# peaks_v02.net
KiCad netlist of a schematic drawn in EAGLE
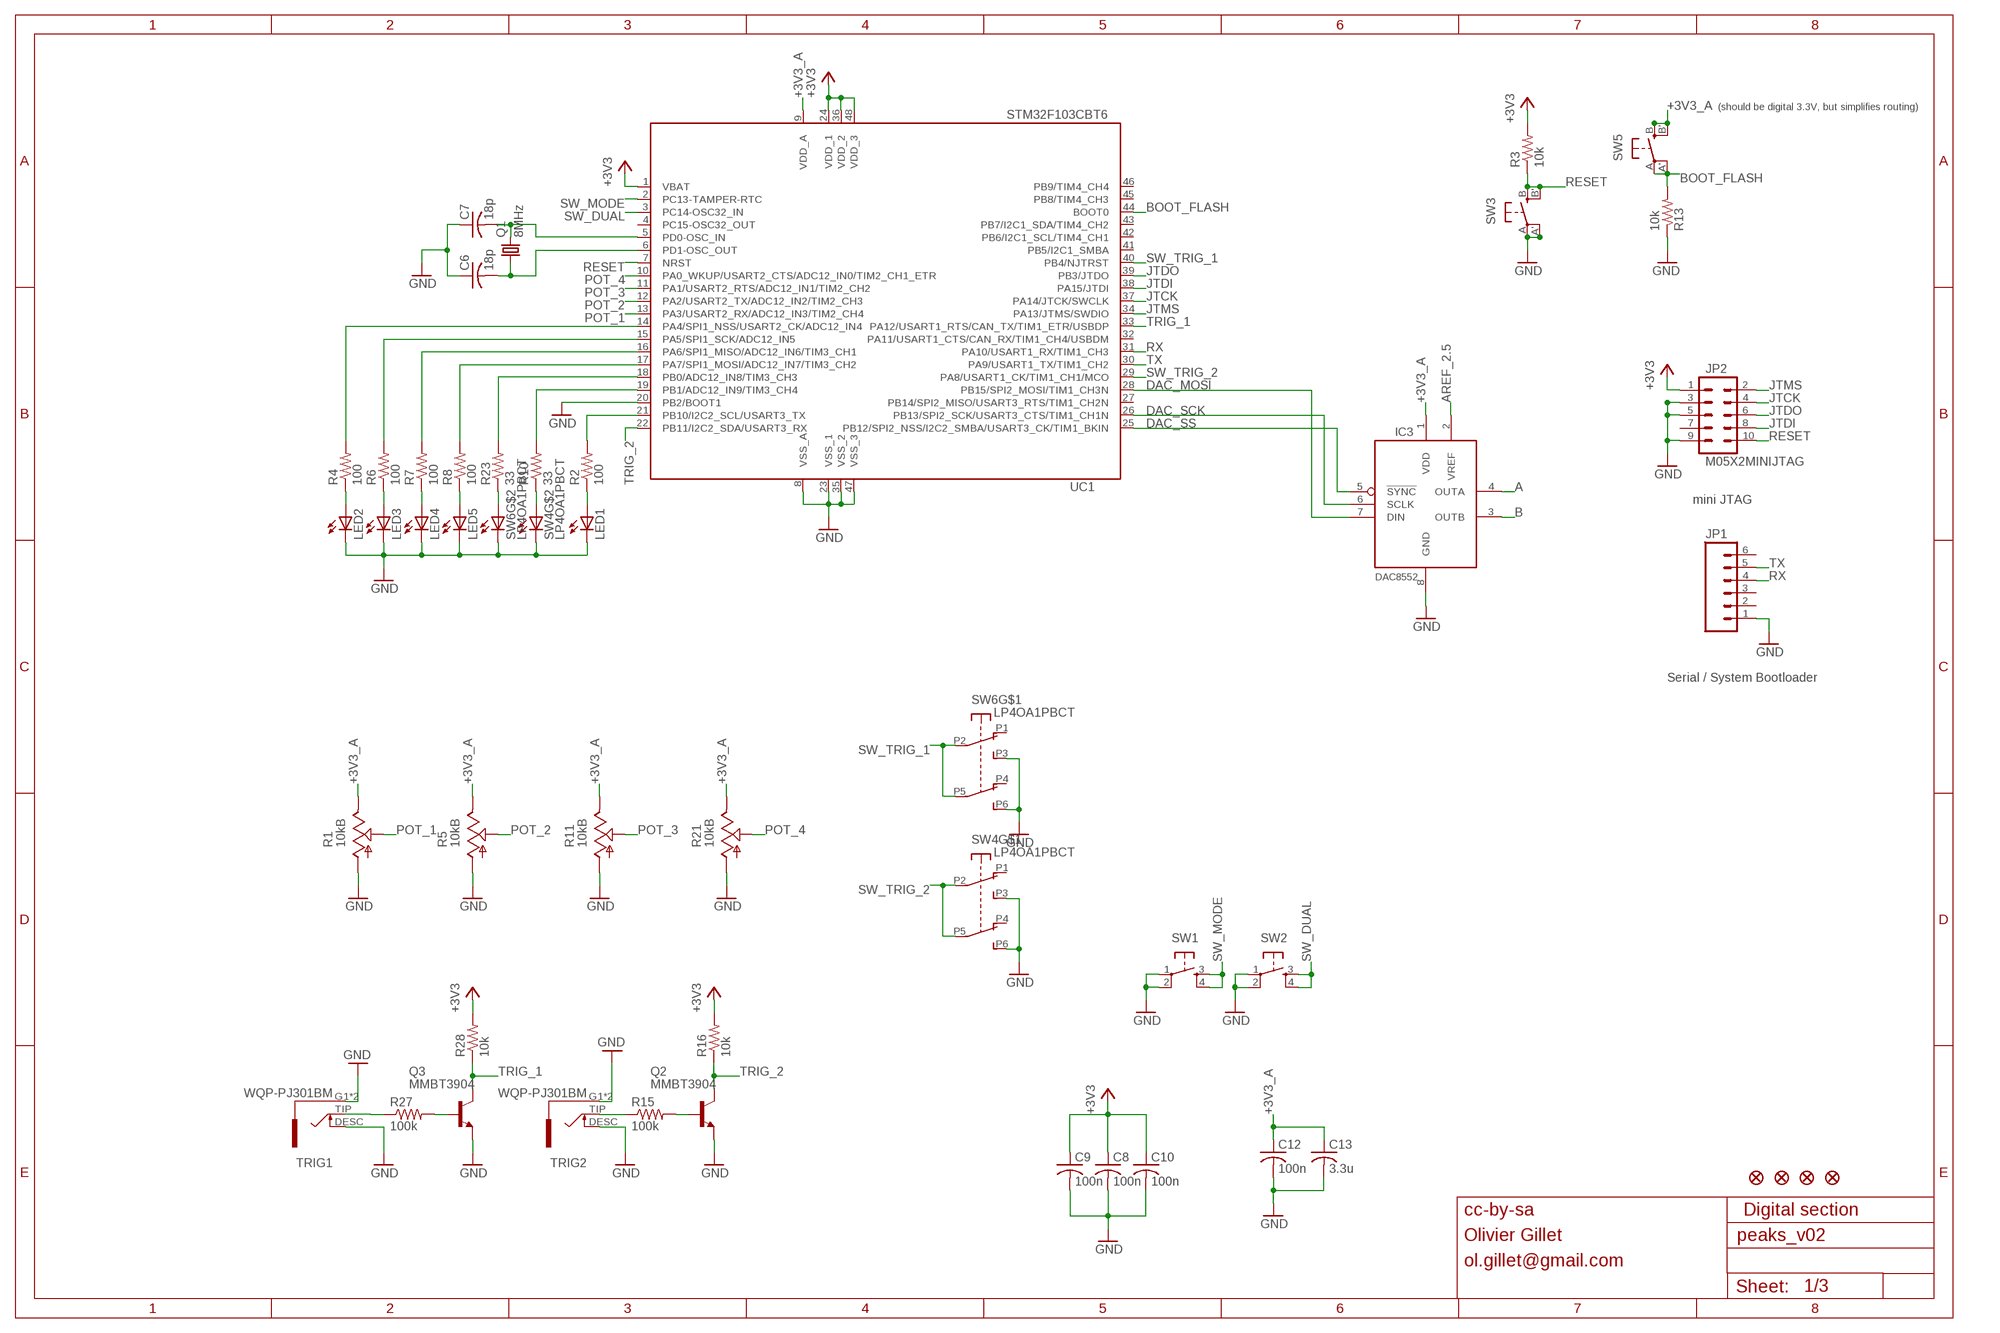
[diagram p0: schematic, sheet 1]
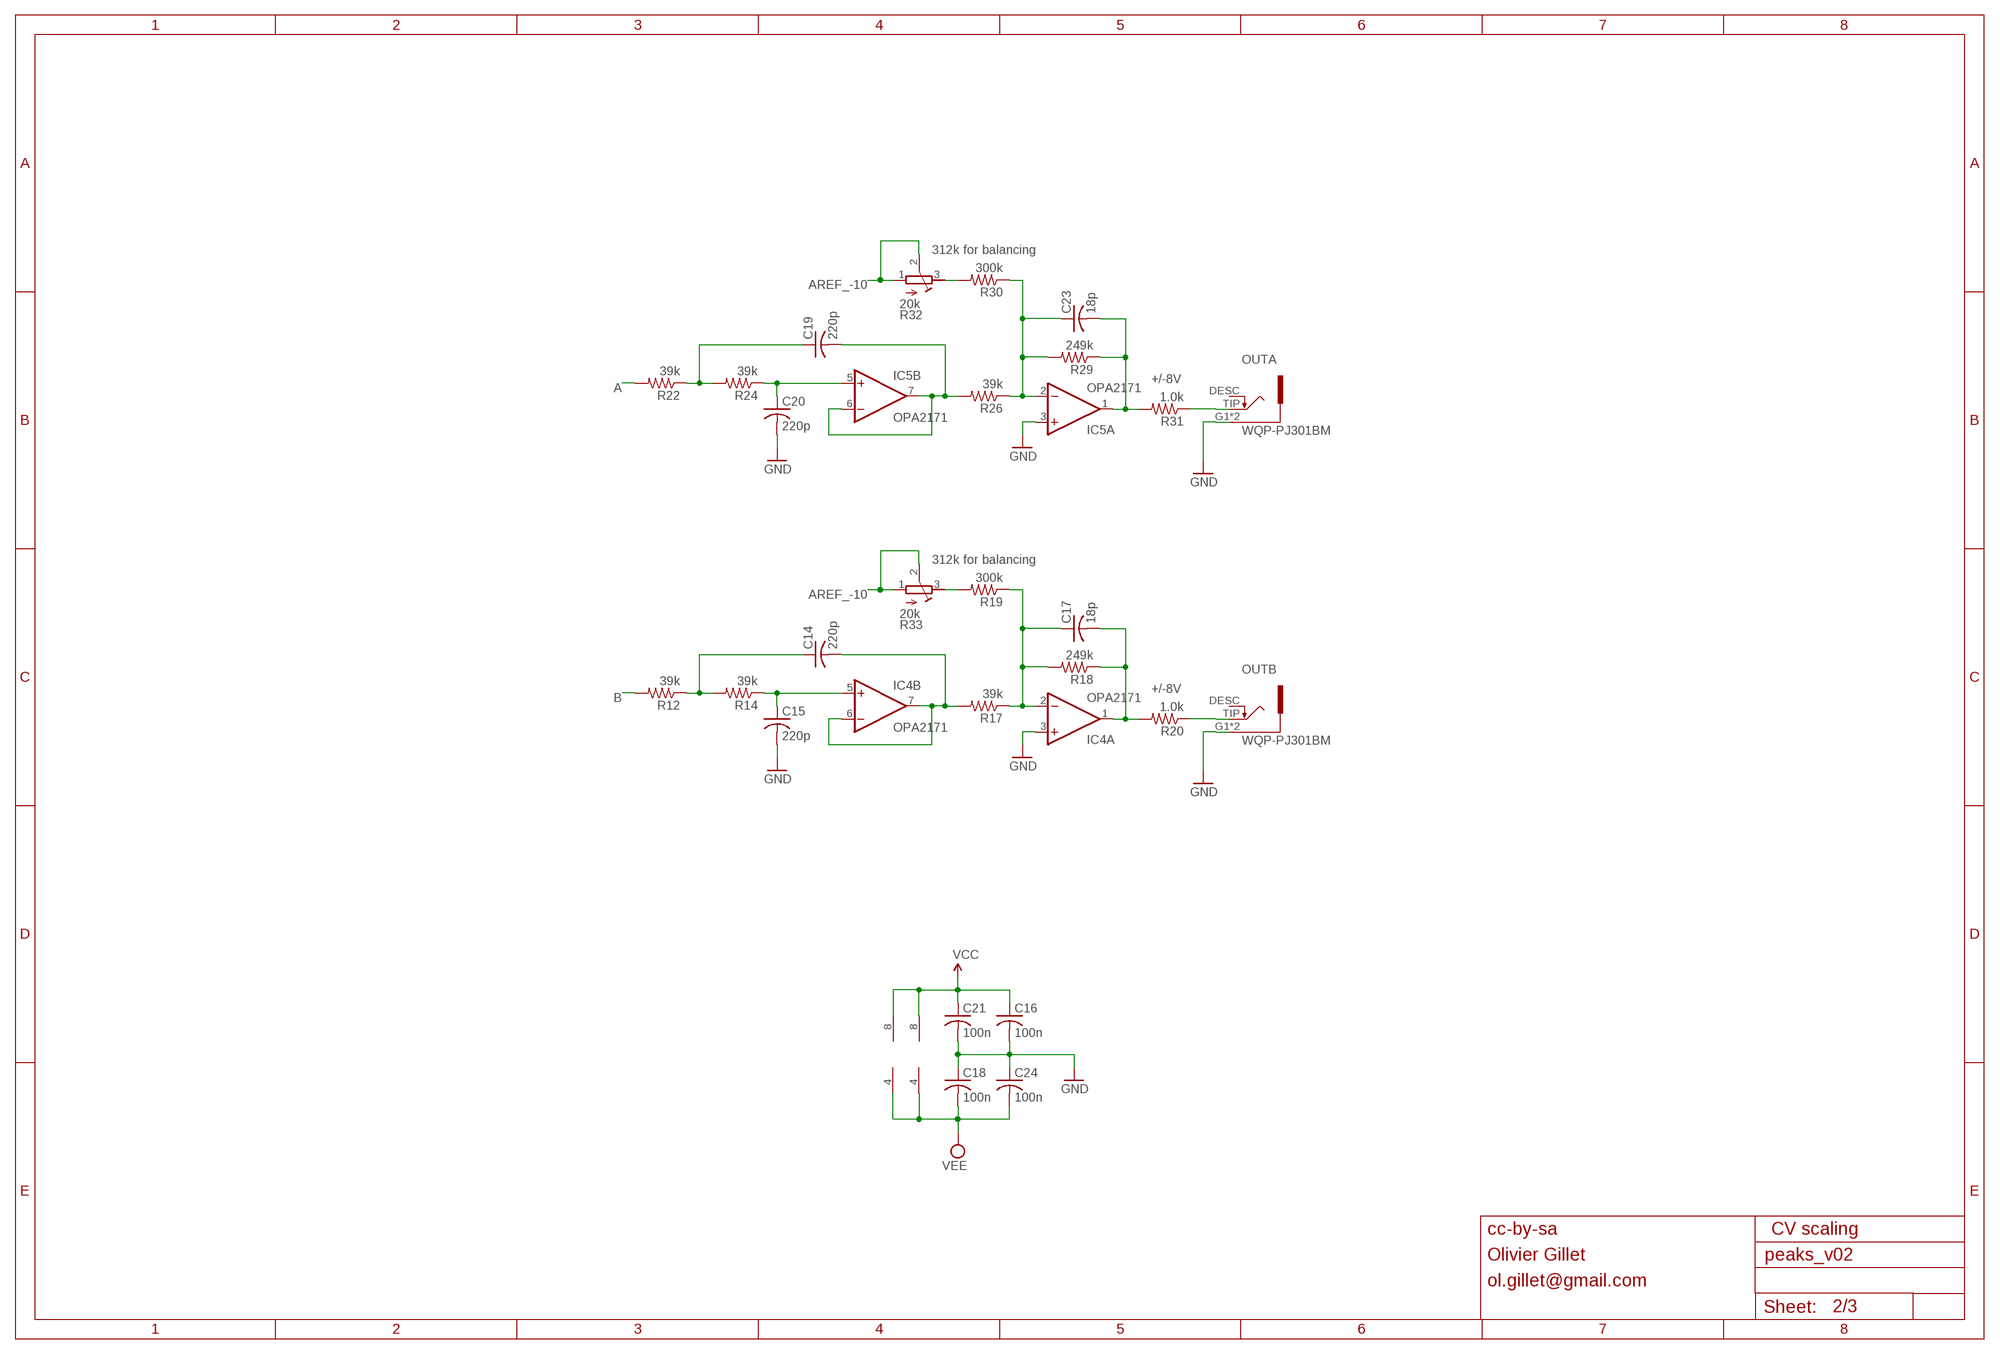
[diagram p1: schematic, sheet 2]
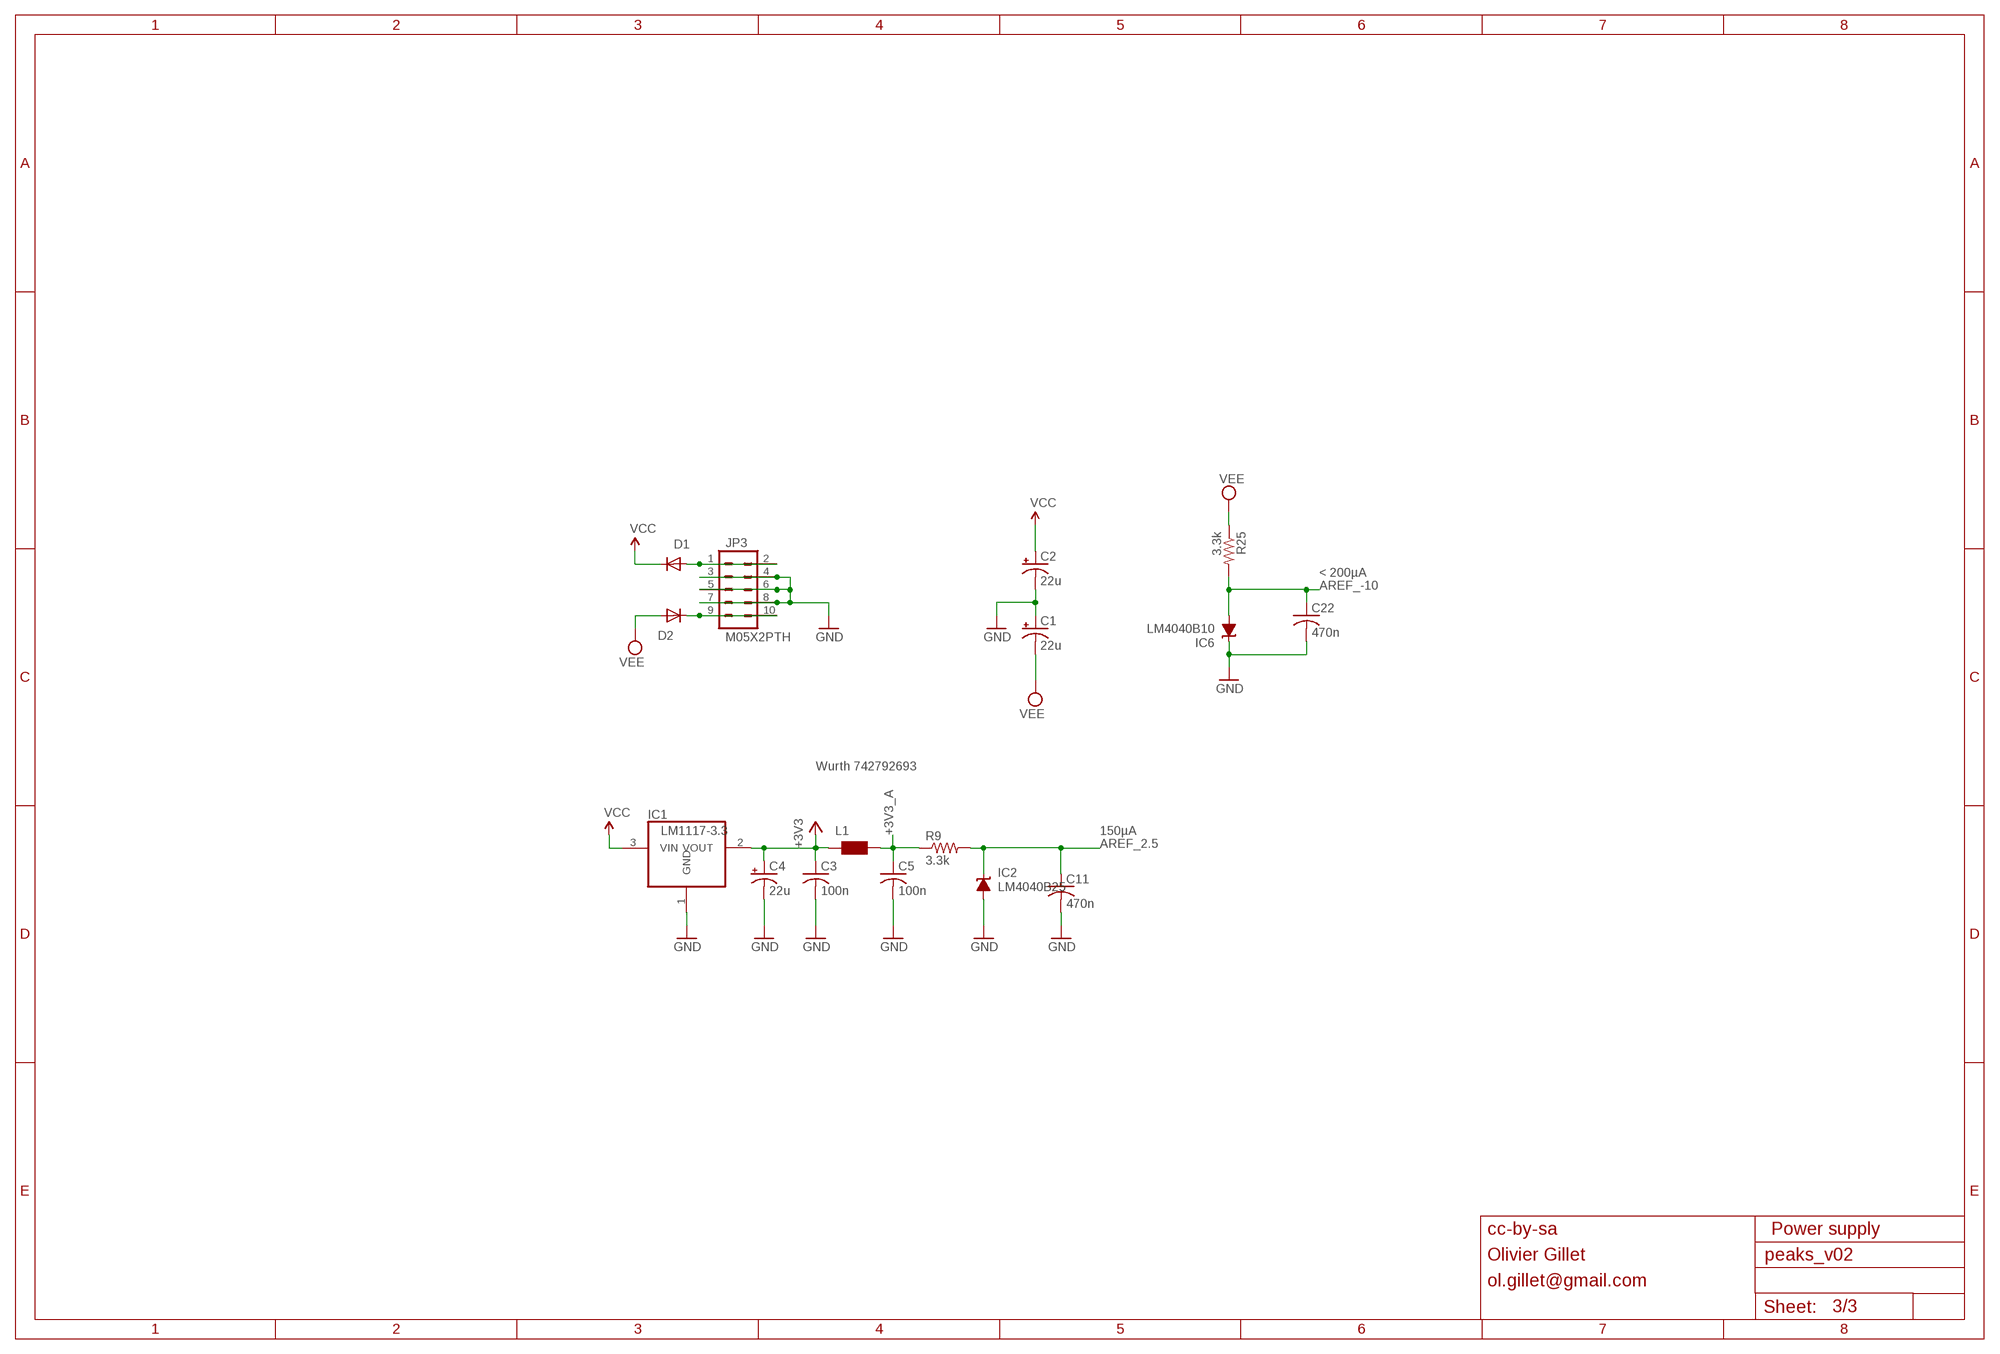
[diagram p2: schematic, sheet 3]

(export (version "E")
  (design (tool "Eeschema 10.0.6"))
  (components
    (comp (ref "C6")
      (value "18p")
      (footprint "eagle-import:C0603")
      (libsource (lib "eagle-import") (part "C-USC0603"))
    )
    (comp (ref "C7")
      (value "18p")
      (footprint "eagle-import:C0603")
      (libsource (lib "eagle-import") (part "C-USC0603"))
    )
    (comp (ref "C8")
      (value "100n")
      (footprint "eagle-import:C0603")
      (libsource (lib "eagle-import") (part "C-USC0603"))
    )
    (comp (ref "C9")
      (value "100n")
      (footprint "eagle-import:C0603")
      (libsource (lib "eagle-import") (part "C-USC0603"))
    )
    (comp (ref "C10")
      (value "100n")
      (footprint "eagle-import:C0603")
      (libsource (lib "eagle-import") (part "C-USC0603"))
    )
    (comp (ref "C12")
      (value "100n")
      (footprint "eagle-import:C0603")
      (libsource (lib "eagle-import") (part "C-USC0603"))
    )
    (comp (ref "C13")
      (value "3.3u")
      (footprint "eagle-import:C0603")
      (libsource (lib "eagle-import") (part "C-USC0603"))
    )
    (comp (ref "F1")
      (value "FIDUCIAL1X2")
      (footprint "eagle-import:FIDUCIAL-1X2")
      (libsource (lib "eagle-import") (part "FIDUCIAL1X2"))
    )
    (comp (ref "F2")
      (value "FIDUCIAL1X2")
      (footprint "eagle-import:FIDUCIAL-1X2")
      (libsource (lib "eagle-import") (part "FIDUCIAL1X2"))
    )
    (comp (ref "F3")
      (value "FIDUCIAL1X2")
      (footprint "eagle-import:FIDUCIAL-1X2")
      (libsource (lib "eagle-import") (part "FIDUCIAL1X2"))
    )
    (comp (ref "F4")
      (value "FIDUCIAL1X2")
      (footprint "eagle-import:FIDUCIAL-1X2")
      (libsource (lib "eagle-import") (part "FIDUCIAL1X2"))
    )
    (comp (ref "IC3")
      (value "DAC8552")
      (footprint "eagle-import:MSOP-8")
      (libsource (lib "eagle-import") (part "DAC8552"))
    )
    (comp (ref "JP1")
      (value "M06SIP")
      (footprint "eagle-import:1X06")
      (libsource (lib "eagle-import") (part "M06SIP"))
    )
    (comp (ref "JP2")
      (value "M05X2MINIJTAG")
      (footprint "eagle-import:2X5-1.27")
      (libsource (lib "eagle-import") (part "M05X2MINIJTAG"))
    )
    (comp (ref "LED1")
      (value "LED3MM")
      (footprint "eagle-import:LED3MM")
      (libsource (lib "eagle-import") (part "LED3MM"))
    )
    (comp (ref "LED2")
      (value "LED3MM")
      (footprint "eagle-import:LED3MM")
      (libsource (lib "eagle-import") (part "LED3MM"))
    )
    (comp (ref "LED3")
      (value "LED3MM")
      (footprint "eagle-import:LED3MM")
      (libsource (lib "eagle-import") (part "LED3MM"))
    )
    (comp (ref "LED4")
      (value "LED3MM")
      (footprint "eagle-import:LED3MM")
      (libsource (lib "eagle-import") (part "LED3MM"))
    )
    (comp (ref "LED5")
      (value "LED3MM")
      (footprint "eagle-import:LED3MM")
      (libsource (lib "eagle-import") (part "LED3MM"))
    )
    (comp (ref "Q1")
      (value "8MHz")
      (footprint "eagle-import:HC49UP")
      (libsource (lib "eagle-import") (part "CRYSTALHC49UP"))
    )
    (comp (ref "Q2")
      (value "MMBT3904")
      (footprint "eagle-import:SOT23-BEC")
      (libsource (lib "eagle-import") (part "-NPN-SOT23-BECMMBT3904LT1"))
    )
    (comp (ref "Q3")
      (value "MMBT3904")
      (footprint "eagle-import:SOT23-BEC")
      (libsource (lib "eagle-import") (part "-NPN-SOT23-BECMMBT3904LT1"))
    )
    (comp (ref "R1")
      (value "10kB")
      (footprint "eagle-import:ALPS_POT_VERTICAL_PS")
      (libsource (lib "eagle-import") (part "POT_USVERTICAL_PS"))
    )
    (comp (ref "R2")
      (value "100")
      (footprint "eagle-import:R0603")
      (libsource (lib "eagle-import") (part "R-US_R0603"))
    )
    (comp (ref "R3")
      (value "10k")
      (footprint "eagle-import:R0603")
      (libsource (lib "eagle-import") (part "R-US_R0603"))
    )
    (comp (ref "R4")
      (value "100")
      (footprint "eagle-import:R0603")
      (libsource (lib "eagle-import") (part "R-US_R0603"))
    )
    (comp (ref "R5")
      (value "10kB")
      (footprint "eagle-import:ALPS_POT_VERTICAL_PS")
      (libsource (lib "eagle-import") (part "POT_USVERTICAL_PS"))
    )
    (comp (ref "R6")
      (value "100")
      (footprint "eagle-import:R0603")
      (libsource (lib "eagle-import") (part "R-US_R0603"))
    )
    (comp (ref "R7")
      (value "100")
      (footprint "eagle-import:R0603")
      (libsource (lib "eagle-import") (part "R-US_R0603"))
    )
    (comp (ref "R8")
      (value "100")
      (footprint "eagle-import:R0603")
      (libsource (lib "eagle-import") (part "R-US_R0603"))
    )
    (comp (ref "R10")
      (value "33")
      (footprint "eagle-import:R0603")
      (libsource (lib "eagle-import") (part "R-US_R0603"))
    )
    (comp (ref "R11")
      (value "10kB")
      (footprint "eagle-import:ALPS_POT_VERTICAL_PS")
      (libsource (lib "eagle-import") (part "POT_USVERTICAL_PS"))
    )
    (comp (ref "R13")
      (value "10k")
      (footprint "eagle-import:R0603")
      (libsource (lib "eagle-import") (part "R-US_R0603"))
    )
    (comp (ref "R15")
      (value "100k")
      (footprint "eagle-import:R0603")
      (libsource (lib "eagle-import") (part "R-US_R0603"))
    )
    (comp (ref "R16")
      (value "10k")
      (footprint "eagle-import:R0603")
      (libsource (lib "eagle-import") (part "R-US_R0603"))
    )
    (comp (ref "R21")
      (value "10kB")
      (footprint "eagle-import:ALPS_POT_VERTICAL_PS")
      (libsource (lib "eagle-import") (part "POT_USVERTICAL_PS"))
    )
    (comp (ref "R23")
      (value "33")
      (footprint "eagle-import:R0603")
      (libsource (lib "eagle-import") (part "R-US_R0603"))
    )
    (comp (ref "R27")
      (value "100k")
      (footprint "eagle-import:R0603")
      (libsource (lib "eagle-import") (part "R-US_R0603"))
    )
    (comp (ref "R28")
      (value "10k")
      (footprint "eagle-import:R0603")
      (libsource (lib "eagle-import") (part "R-US_R0603"))
    )
    (comp (ref "SW1")
      (value "TAC_SWITCHPTH")
      (footprint "eagle-import:TACTILE-PTH")
      (libsource (lib "eagle-import") (part "TAC_SWITCHPTH"))
    )
    (comp (ref "SW2")
      (value "TAC_SWITCHPTH")
      (footprint "eagle-import:TACTILE-PTH")
      (libsource (lib "eagle-import") (part "TAC_SWITCHPTH"))
    )
    (comp (ref "SW3")
      (value "EVQQ2")
      (footprint "eagle-import:EVQ-Q2")
      (libsource (lib "eagle-import") (part "EVQQ2"))
    )
    (comp (ref "SW4")
      (value "LP4OA1PBCT")
      (footprint "eagle-import:LP4OA1PBCT")
      (libsource (lib "eagle-import") (part "LP4OA1PBCT"))
    )
    (comp (ref "SW5")
      (value "EVQQ2")
      (footprint "eagle-import:EVQ-Q2")
      (libsource (lib "eagle-import") (part "EVQQ2"))
    )
    (comp (ref "SW6")
      (value "LP4OA1PBCT")
      (footprint "eagle-import:LP4OA1PBCT")
      (libsource (lib "eagle-import") (part "LP4OA1PBCT"))
    )
    (comp (ref "TRIG1")
      (value "WQP-PJ301BM")
      (footprint "eagle-import:WQP-PJ301BM")
      (libsource (lib "eagle-import") (part "WQP-PJ301BM"))
    )
    (comp (ref "TRIG2")
      (value "WQP-PJ301BM")
      (footprint "eagle-import:WQP-PJ301BM")
      (libsource (lib "eagle-import") (part "WQP-PJ301BM"))
    )
    (comp (ref "UC1")
      (value "STM32F103CBT6")
      (footprint "eagle-import:LQFP48")
      (libsource (lib "eagle-import") (part "STM32F103CB"))
    )
    (comp (ref "C1")
      (value "22u")
      (footprint "eagle-import:PANASONIC_C")
      (libsource (lib "eagle-import") (part "CPOL-USC"))
    )
    (comp (ref "C2")
      (value "22u")
      (footprint "eagle-import:PANASONIC_C")
      (libsource (lib "eagle-import") (part "CPOL-USC"))
    )
    (comp (ref "C3")
      (value "100n")
      (footprint "eagle-import:C0603")
      (libsource (lib "eagle-import") (part "C-USC0603"))
    )
    (comp (ref "C4")
      (value "22u")
      (footprint "eagle-import:PANASONIC_C")
      (libsource (lib "eagle-import") (part "CPOL-USC"))
    )
    (comp (ref "C5")
      (value "100n")
      (footprint "eagle-import:C0603")
      (libsource (lib "eagle-import") (part "C-USC0603"))
    )
    (comp (ref "C11")
      (value "470n")
      (footprint "eagle-import:C0603")
      (libsource (lib "eagle-import") (part "C-USC0603"))
    )
    (comp (ref "C22")
      (value "470n")
      (footprint "eagle-import:C0603")
      (libsource (lib "eagle-import") (part "C-USC0603"))
    )
    (comp (ref "D1")
      (value "1N5819HW")
      (footprint "eagle-import:SOD123")
      (libsource (lib "eagle-import") (part "DIODE-SOD123"))
    )
    (comp (ref "D2")
      (value "1N5819HW")
      (footprint "eagle-import:SOD123")
      (libsource (lib "eagle-import") (part "DIODE-SOD123"))
    )
    (comp (ref "IC1")
      (value "LM1117-3.3")
      (footprint "eagle-import:SOT223")
      (libsource (lib "eagle-import") (part "REG1117"))
    )
    (comp (ref "IC2")
      (value "LM4040B25")
      (footprint "eagle-import:DBZ_R-PDSO-G3")
      (libsource (lib "eagle-import") (part "LM4041DBZB12"))
    )
    (comp (ref "IC6")
      (value "LM4040B10")
      (footprint "eagle-import:DBZ_R-PDSO-G3")
      (libsource (lib "eagle-import") (part "LM4041DBZB12"))
    )
    (comp (ref "JP3")
      (value "M05X2PTH")
      (footprint "eagle-import:AVR_ICSP")
      (libsource (lib "eagle-import") (part "M05X2PTH"))
    )
    (comp (ref "L1")
      (value "WE-CBF_0603")
      (footprint "eagle-import:0603")
      (libsource (lib "eagle-import") (part "WE-CBF_0603"))
    )
    (comp (ref "R9")
      (value "3.3k")
      (footprint "eagle-import:R0603")
      (libsource (lib "eagle-import") (part "R-US_R0603"))
    )
    (comp (ref "R25")
      (value "3.3k")
      (footprint "eagle-import:R0603")
      (libsource (lib "eagle-import") (part "R-US_R0603"))
    )
    (comp (ref "C14")
      (value "220p")
      (footprint "eagle-import:C0603")
      (libsource (lib "eagle-import") (part "C-USC0603"))
    )
    (comp (ref "C15")
      (value "220p")
      (footprint "eagle-import:C0603")
      (libsource (lib "eagle-import") (part "C-USC0603"))
    )
    (comp (ref "C16")
      (value "100n")
      (footprint "eagle-import:C0603")
      (libsource (lib "eagle-import") (part "C-USC0603"))
    )
    (comp (ref "C17")
      (value "18p")
      (footprint "eagle-import:C0603")
      (libsource (lib "eagle-import") (part "C-USC0603"))
    )
    (comp (ref "C18")
      (value "100n")
      (footprint "eagle-import:C0603")
      (libsource (lib "eagle-import") (part "C-USC0603"))
    )
    (comp (ref "C19")
      (value "220p")
      (footprint "eagle-import:C0603")
      (libsource (lib "eagle-import") (part "C-USC0603"))
    )
    (comp (ref "C20")
      (value "220p")
      (footprint "eagle-import:C0603")
      (libsource (lib "eagle-import") (part "C-USC0603"))
    )
    (comp (ref "C21")
      (value "100n")
      (footprint "eagle-import:C0603")
      (libsource (lib "eagle-import") (part "C-USC0603"))
    )
    (comp (ref "C23")
      (value "18p")
      (footprint "eagle-import:C0603")
      (libsource (lib "eagle-import") (part "C-USC0603"))
    )
    (comp (ref "C24")
      (value "100n")
      (footprint "eagle-import:C0603")
      (libsource (lib "eagle-import") (part "C-USC0603"))
    )
    (comp (ref "IC4")
      (value "OPA2171")
      (footprint "eagle-import:SO08")
      (libsource (lib "eagle-import") (part "TL072D"))
    )
    (comp (ref "IC5")
      (value "OPA2171")
      (footprint "eagle-import:SO08")
      (libsource (lib "eagle-import") (part "TL072D"))
    )
    (comp (ref "OUTA")
      (value "WQP-PJ301BM")
      (footprint "eagle-import:WQP-PJ301BM")
      (libsource (lib "eagle-import") (part "WQP-PJ301BM"))
    )
    (comp (ref "OUTB")
      (value "WQP-PJ301BM")
      (footprint "eagle-import:WQP-PJ301BM")
      (libsource (lib "eagle-import") (part "WQP-PJ301BM"))
    )
    (comp (ref "R12")
      (value "39k")
      (footprint "eagle-import:R0603")
      (libsource (lib "eagle-import") (part "R-US_R0603"))
    )
    (comp (ref "R14")
      (value "39k")
      (footprint "eagle-import:R0603")
      (libsource (lib "eagle-import") (part "R-US_R0603"))
    )
    (comp (ref "R17")
      (value "39k")
      (footprint "eagle-import:R0603")
      (libsource (lib "eagle-import") (part "R-US_R0603"))
    )
    (comp (ref "R18")
      (value "249k")
      (footprint "eagle-import:R0603")
      (libsource (lib "eagle-import") (part "R-US_R0603"))
    )
    (comp (ref "R19")
      (value "300k")
      (footprint "eagle-import:R0603")
      (libsource (lib "eagle-import") (part "R-US_R0603"))
    )
    (comp (ref "R20")
      (value "1.0k")
      (footprint "eagle-import:R0603")
      (libsource (lib "eagle-import") (part "R-US_R0603"))
    )
    (comp (ref "R22")
      (value "39k")
      (footprint "eagle-import:R0603")
      (libsource (lib "eagle-import") (part "R-US_R0603"))
    )
    (comp (ref "R24")
      (value "39k")
      (footprint "eagle-import:R0603")
      (libsource (lib "eagle-import") (part "R-US_R0603"))
    )
    (comp (ref "R26")
      (value "39k")
      (footprint "eagle-import:R0603")
      (libsource (lib "eagle-import") (part "R-US_R0603"))
    )
    (comp (ref "R29")
      (value "249k")
      (footprint "eagle-import:R0603")
      (libsource (lib "eagle-import") (part "R-US_R0603"))
    )
    (comp (ref "R30")
      (value "300k")
      (footprint "eagle-import:R0603")
      (libsource (lib "eagle-import") (part "R-US_R0603"))
    )
    (comp (ref "R31")
      (value "1.0k")
      (footprint "eagle-import:R0603")
      (libsource (lib "eagle-import") (part "R-US_R0603"))
    )
    (comp (ref "R32")
      (value "20k")
      (footprint "eagle-import:RTRIM3296W")
      (libsource (lib "eagle-import") (part "R-TRIMM3296W"))
    )
    (comp (ref "R33")
      (value "20k")
      (footprint "eagle-import:RTRIM3296W")
      (libsource (lib "eagle-import") (part "R-TRIMM3296W"))
    )
  )
  (nets
    (net (code "1") (name "+3V3") (class "Default")
      (node (ref "C10") (pin "1") (pinfunction "1_1") (pintype "passive"))
      (node (ref "C3") (pin "1") (pinfunction "1_1") (pintype "passive"))
      (node (ref "C4") (pin "+") (pinfunction "+_+") (pintype "passive"))
      (node (ref "C8") (pin "1") (pinfunction "1_1") (pintype "passive"))
      (node (ref "C9") (pin "1") (pinfunction "1_1") (pintype "passive"))
      (node (ref "IC1") (pin "2") (pinfunction "VOUT_2") (pintype "output"))
      (node (ref "JP2") (pin "1") (pinfunction "1_1") (pintype "passive"))
      (node (ref "L1") (pin "1") (pinfunction "1_1") (pintype "passive"))
      (node (ref "R16") (pin "2") (pinfunction "2_2") (pintype "passive"))
      (node (ref "R28") (pin "2") (pinfunction "2_2") (pintype "passive"))
      (node (ref "R3") (pin "2") (pinfunction "2_2") (pintype "passive"))
      (node (ref "UC1") (pin "1") (pinfunction "VBAT_1") (pintype "power_in"))
      (node (ref "UC1") (pin "24") (pinfunction "VDD_1_24") (pintype "power_in"))
      (node (ref "UC1") (pin "36") (pinfunction "VDD_2_36") (pintype "power_in"))
      (node (ref "UC1") (pin "48") (pinfunction "VDD_3_48") (pintype "power_in"))
    )
    (net (code "2") (name "+3V3_A") (class "Default")
      (node (ref "C12") (pin "1") (pinfunction "1_1") (pintype "passive"))
      (node (ref "C13") (pin "1") (pinfunction "1_1") (pintype "passive"))
      (node (ref "C5") (pin "1") (pinfunction "1_1") (pintype "passive"))
      (node (ref "IC3") (pin "1") (pinfunction "VDD_1") (pintype "power_in"))
      (node (ref "L1") (pin "2") (pinfunction "2_2") (pintype "passive"))
      (node (ref "R1") (pin "P$1") (pinfunction "E_P$1") (pintype "passive"))
      (node (ref "R11") (pin "P$1") (pinfunction "E_P$1") (pintype "passive"))
      (node (ref "R21") (pin "P$1") (pinfunction "E_P$1") (pintype "passive"))
      (node (ref "R5") (pin "P$1") (pinfunction "E_P$1") (pintype "passive"))
      (node (ref "R9") (pin "1") (pinfunction "1_1") (pintype "passive"))
      (node (ref "SW5") (pin "B") (pinfunction "S_B") (pintype "passive"))
      (node (ref "SW5") (pin "B'") (pinfunction "S1_B'") (pintype "passive"))
      (node (ref "UC1") (pin "9") (pinfunction "VDD_A_9") (pintype "power_in"))
    )
    (net (code "3") (name "A") (class "Default")
      (node (ref "IC3") (pin "4") (pinfunction "OUTA_4") (pintype "output"))
      (node (ref "R22") (pin "2") (pinfunction "2_2") (pintype "passive"))
    )
    (net (code "4") (name "AREF_-10") (class "Default")
      (node (ref "C22") (pin "1") (pinfunction "1_1") (pintype "passive"))
      (node (ref "IC6") (pin "2") (pinfunction "A_2") (pintype "passive"))
      (node (ref "R25") (pin "2") (pinfunction "2_2") (pintype "passive"))
      (node (ref "R32") (pin "1") (pinfunction "E_1") (pintype "passive"))
      (node (ref "R32") (pin "2") (pinfunction "S_2") (pintype "passive"))
      (node (ref "R33") (pin "1") (pinfunction "E_1") (pintype "passive"))
      (node (ref "R33") (pin "2") (pinfunction "S_2") (pintype "passive"))
    )
    (net (code "5") (name "AREF_2.5") (class "Default")
      (node (ref "C11") (pin "1") (pinfunction "1_1") (pintype "passive"))
      (node (ref "IC2") (pin "1") (pinfunction "C_1") (pintype "passive"))
      (node (ref "IC3") (pin "2") (pinfunction "VREF_2") (pintype "power_in"))
      (node (ref "R9") (pin "2") (pinfunction "2_2") (pintype "passive"))
    )
    (net (code "6") (name "B") (class "Default")
      (node (ref "IC3") (pin "3") (pinfunction "OUTB_3") (pintype "input"))
      (node (ref "R12") (pin "2") (pinfunction "2_2") (pintype "passive"))
    )
    (net (code "7") (name "BOOT_FLASH") (class "Default")
      (node (ref "R13") (pin "2") (pinfunction "2_2") (pintype "passive"))
      (node (ref "SW5") (pin "A") (pinfunction "P_A") (pintype "passive"))
      (node (ref "SW5") (pin "A'") (pinfunction "P1_A'") (pintype "passive"))
      (node (ref "UC1") (pin "44") (pinfunction "BOOT0_44") (pintype "input"))
    )
    (net (code "8") (name "DAC_MOSI") (class "Default")
      (node (ref "IC3") (pin "7") (pinfunction "DIN_7") (pintype "bidirectional"))
      (node (ref "UC1") (pin "28") (pinfunction "PB15/SPI2_MOSI/TIM1_CH3N_28") (pintype "input"))
    )
    (net (code "9") (name "DAC_SCK") (class "Default")
      (node (ref "IC3") (pin "6") (pinfunction "SCLK_6") (pintype "bidirectional"))
      (node (ref "UC1") (pin "26") (pinfunction "PB13/SPI2_SCK/USART3_CTS/TIM1_CH1N_26") (pintype "input"))
    )
    (net (code "10") (name "DAC_SS") (class "Default")
      (node (ref "IC3") (pin "5") (pinfunction "~{SYNC}_5") (pintype "bidirectional"))
      (node (ref "UC1") (pin "25") (pinfunction "PB12/SPI2_NSS/I2C2_SMBA/USART3_CK/TIM1_BKIN_25") (pintype "input"))
    )
    (net (code "11") (name "GND") (class "Default")
      (node (ref "C1") (pin "+") (pinfunction "+_+") (pintype "passive"))
      (node (ref "C10") (pin "2") (pinfunction "2_2") (pintype "passive"))
      (node (ref "C11") (pin "2") (pinfunction "2_2") (pintype "passive"))
      (node (ref "C12") (pin "2") (pinfunction "2_2") (pintype "passive"))
      (node (ref "C13") (pin "2") (pinfunction "2_2") (pintype "passive"))
      (node (ref "C15") (pin "2") (pinfunction "2_2") (pintype "passive"))
      (node (ref "C16") (pin "2") (pinfunction "2_2") (pintype "passive"))
      (node (ref "C18") (pin "1") (pinfunction "1_1") (pintype "passive"))
      (node (ref "C2") (pin "-") (pinfunction "-_-") (pintype "passive"))
      (node (ref "C20") (pin "2") (pinfunction "2_2") (pintype "passive"))
      (node (ref "C21") (pin "2") (pinfunction "2_2") (pintype "passive"))
      (node (ref "C22") (pin "2") (pinfunction "2_2") (pintype "passive"))
      (node (ref "C24") (pin "1") (pinfunction "1_1") (pintype "passive"))
      (node (ref "C3") (pin "2") (pinfunction "2_2") (pintype "passive"))
      (node (ref "C4") (pin "-") (pinfunction "-_-") (pintype "passive"))
      (node (ref "C5") (pin "2") (pinfunction "2_2") (pintype "passive"))
      (node (ref "C6") (pin "1") (pinfunction "1_1") (pintype "passive"))
      (node (ref "C7") (pin "1") (pinfunction "1_1") (pintype "passive"))
      (node (ref "C8") (pin "2") (pinfunction "2_2") (pintype "passive"))
      (node (ref "C9") (pin "2") (pinfunction "2_2") (pintype "passive"))
      (node (ref "IC1") (pin "1") (pinfunction "GND_1") (pintype "power_in"))
      (node (ref "IC2") (pin "2") (pinfunction "A_2") (pintype "passive"))
      (node (ref "IC3") (pin "8") (pinfunction "GND_8") (pintype "power_in"))
      (node (ref "IC4") (pin "3") (pinfunction "+IN_3") (pintype "input"))
      (node (ref "IC5") (pin "3") (pinfunction "+IN_3") (pintype "input"))
      (node (ref "IC6") (pin "1") (pinfunction "C_1") (pintype "passive"))
      (node (ref "JP1") (pin "1") (pinfunction "1_1") (pintype "passive"))
      (node (ref "JP2") (pin "3") (pinfunction "3_3") (pintype "passive"))
      (node (ref "JP2") (pin "5") (pinfunction "5_5") (pintype "passive"))
      (node (ref "JP2") (pin "9") (pinfunction "9_9") (pintype "passive"))
      (node (ref "JP3") (pin "3") (pinfunction "3_3") (pintype "passive"))
      (node (ref "JP3") (pin "4") (pinfunction "4_4") (pintype "passive"))
      (node (ref "JP3") (pin "5") (pinfunction "5_5") (pintype "passive"))
      (node (ref "JP3") (pin "6") (pinfunction "6_6") (pintype "passive"))
      (node (ref "JP3") (pin "7") (pinfunction "7_7") (pintype "passive"))
      (node (ref "JP3") (pin "8") (pinfunction "8_8") (pintype "passive"))
      (node (ref "LED1") (pin "K") (pinfunction "C_K") (pintype "passive"))
      (node (ref "LED2") (pin "K") (pinfunction "C_K") (pintype "passive"))
      (node (ref "LED3") (pin "K") (pinfunction "C_K") (pintype "passive"))
      (node (ref "LED4") (pin "K") (pinfunction "C_K") (pintype "passive"))
      (node (ref "LED5") (pin "K") (pinfunction "C_K") (pintype "passive"))
      (node (ref "OUTA") (pin "G1") (pinfunction "SLEVE_G1") (pintype "power_in"))
      (node (ref "OUTA") (pin "G2") (pinfunction "SLEVE_G2") (pintype "power_in"))
      (node (ref "OUTB") (pin "G1") (pinfunction "SLEVE_G1") (pintype "power_in"))
      (node (ref "OUTB") (pin "G2") (pinfunction "SLEVE_G2") (pintype "power_in"))
      (node (ref "Q2") (pin "E") (pinfunction "E_E") (pintype "passive"))
      (node (ref "Q3") (pin "E") (pinfunction "E_E") (pintype "passive"))
      (node (ref "R1") (pin "P$3") (pinfunction "A_P$3") (pintype "passive"))
      (node (ref "R11") (pin "P$3") (pinfunction "A_P$3") (pintype "passive"))
      (node (ref "R13") (pin "1") (pinfunction "1_1") (pintype "passive"))
      (node (ref "R21") (pin "P$3") (pinfunction "A_P$3") (pintype "passive"))
      (node (ref "R5") (pin "P$3") (pinfunction "A_P$3") (pintype "passive"))
      (node (ref "SW1") (pin "1") (pinfunction "1_1") (pintype "passive"))
      (node (ref "SW1") (pin "2") (pinfunction "2_2") (pintype "passive"))
      (node (ref "SW2") (pin "1") (pinfunction "1_1") (pintype "passive"))
      (node (ref "SW2") (pin "2") (pinfunction "2_2") (pintype "passive"))
      (node (ref "SW3") (pin "A") (pinfunction "P_A") (pintype "passive"))
      (node (ref "SW3") (pin "A'") (pinfunction "P1_A'") (pintype "passive"))
      (node (ref "SW4") (pin "L2") (pinfunction "L2_L2") (pintype "passive"))
      (node (ref "SW4") (pin "P3") (pinfunction "A3_P3") (pintype "passive"))
      (node (ref "SW4") (pin "P6") (pinfunction "B3_P6") (pintype "passive"))
      (node (ref "SW6") (pin "L2") (pinfunction "L2_L2") (pintype "passive"))
      (node (ref "SW6") (pin "P3") (pinfunction "A3_P3") (pintype "passive"))
      (node (ref "SW6") (pin "P6") (pinfunction "B3_P6") (pintype "passive"))
      (node (ref "TRIG1") (pin "DESC") (pinfunction "SWITCH_DESC") (pintype "passive"))
      (node (ref "TRIG1") (pin "G1") (pinfunction "SLEVE_G1") (pintype "power_in"))
      (node (ref "TRIG1") (pin "G2") (pinfunction "SLEVE_G2") (pintype "power_in"))
      (node (ref "TRIG2") (pin "DESC") (pinfunction "SWITCH_DESC") (pintype "passive"))
      (node (ref "TRIG2") (pin "G1") (pinfunction "SLEVE_G1") (pintype "power_in"))
      (node (ref "TRIG2") (pin "G2") (pinfunction "SLEVE_G2") (pintype "power_in"))
      (node (ref "UC1") (pin "20") (pinfunction "PB2/BOOT1_20") (pintype "bidirectional"))
      (node (ref "UC1") (pin "23") (pinfunction "VSS_1_23") (pintype "power_in"))
      (node (ref "UC1") (pin "35") (pinfunction "VSS_2_35") (pintype "power_in"))
      (node (ref "UC1") (pin "47") (pinfunction "VSS_3_47") (pintype "power_in"))
      (node (ref "UC1") (pin "8") (pinfunction "VSS_A_8") (pintype "power_in"))
    )
    (net (code "12") (name "JTCK") (class "Default")
      (node (ref "JP2") (pin "4") (pinfunction "4_4") (pintype "passive"))
      (node (ref "UC1") (pin "37") (pinfunction "PA14/JTCK/SWCLK_37") (pintype "bidirectional"))
    )
    (net (code "13") (name "JTDI") (class "Default")
      (node (ref "JP2") (pin "8") (pinfunction "8_8") (pintype "passive"))
      (node (ref "UC1") (pin "38") (pinfunction "PA15/JTDI_38") (pintype "bidirectional"))
    )
    (net (code "14") (name "JTDO") (class "Default")
      (node (ref "JP2") (pin "6") (pinfunction "6_6") (pintype "passive"))
      (node (ref "UC1") (pin "39") (pinfunction "PB3/JTDO_39") (pintype "bidirectional"))
    )
    (net (code "15") (name "JTMS") (class "Default")
      (node (ref "JP2") (pin "2") (pinfunction "2_2") (pintype "passive"))
      (node (ref "UC1") (pin "34") (pinfunction "PA13/JTMS/SWDIO_34") (pintype "bidirectional"))
    )
    (net (code "16") (name "Net-(C14-Pad1)") (class "Default")
      (node (ref "C14") (pin "1") (pinfunction "1_1") (pintype "passive"))
      (node (ref "R12") (pin "1") (pinfunction "1_1") (pintype "passive"))
      (node (ref "R14") (pin "2") (pinfunction "2_2") (pintype "passive"))
    )
    (net (code "17") (name "Net-(C19-Pad1)") (class "Default")
      (node (ref "C19") (pin "1") (pinfunction "1_1") (pintype "passive"))
      (node (ref "R22") (pin "1") (pinfunction "1_1") (pintype "passive"))
      (node (ref "R24") (pin "2") (pinfunction "2_2") (pintype "passive"))
    )
    (net (code "18") (name "Net-(D1-PadA)") (class "Default")
      (node (ref "D1") (pin "A") (pinfunction "A_A") (pintype "passive"))
      (node (ref "JP3") (pin "1") (pinfunction "1_1") (pintype "passive"))
      (node (ref "JP3") (pin "2") (pinfunction "2_2") (pintype "passive"))
    )
    (net (code "19") (name "Net-(D2-PadC)") (class "Default")
      (node (ref "D2") (pin "C") (pinfunction "C_C") (pintype "passive"))
      (node (ref "JP3") (pin "10") (pinfunction "10_10") (pintype "passive"))
      (node (ref "JP3") (pin "9") (pinfunction "9_9") (pintype "passive"))
    )
    (net (code "20") (name "Net-(IC4A--IN)") (class "Default")
      (node (ref "C17") (pin "1") (pinfunction "1_1") (pintype "passive"))
      (node (ref "IC4") (pin "2") (pinfunction "-IN_2") (pintype "input"))
      (node (ref "R17") (pin "1") (pinfunction "1_1") (pintype "passive"))
      (node (ref "R18") (pin "2") (pinfunction "2_2") (pintype "passive"))
      (node (ref "R19") (pin "1") (pinfunction "1_1") (pintype "passive"))
    )
    (net (code "21") (name "Net-(IC4A-OUT)") (class "Default")
      (node (ref "C17") (pin "2") (pinfunction "2_2") (pintype "passive"))
      (node (ref "IC4") (pin "1") (pinfunction "OUT_1") (pintype "output"))
      (node (ref "R18") (pin "1") (pinfunction "1_1") (pintype "passive"))
      (node (ref "R20") (pin "2") (pinfunction "2_2") (pintype "passive"))
    )
    (net (code "22") (name "Net-(IC4B-+IN)") (class "Default")
      (node (ref "C15") (pin "1") (pinfunction "1_1") (pintype "passive"))
      (node (ref "IC4") (pin "5") (pinfunction "+IN_5") (pintype "input"))
      (node (ref "R14") (pin "1") (pinfunction "1_1") (pintype "passive"))
    )
    (net (code "23") (name "Net-(IC4B--IN)") (class "Default")
      (node (ref "C14") (pin "2") (pinfunction "2_2") (pintype "passive"))
      (node (ref "IC4") (pin "6") (pinfunction "-IN_6") (pintype "input"))
      (node (ref "IC4") (pin "7") (pinfunction "OUT_7") (pintype "output"))
      (node (ref "R17") (pin "2") (pinfunction "2_2") (pintype "passive"))
    )
    (net (code "24") (name "Net-(IC5A--IN)") (class "Default")
      (node (ref "C23") (pin "1") (pinfunction "1_1") (pintype "passive"))
      (node (ref "IC5") (pin "2") (pinfunction "-IN_2") (pintype "input"))
      (node (ref "R26") (pin "1") (pinfunction "1_1") (pintype "passive"))
      (node (ref "R29") (pin "2") (pinfunction "2_2") (pintype "passive"))
      (node (ref "R30") (pin "1") (pinfunction "1_1") (pintype "passive"))
    )
    (net (code "25") (name "Net-(IC5A-OUT)") (class "Default")
      (node (ref "C23") (pin "2") (pinfunction "2_2") (pintype "passive"))
      (node (ref "IC5") (pin "1") (pinfunction "OUT_1") (pintype "output"))
      (node (ref "R29") (pin "1") (pinfunction "1_1") (pintype "passive"))
      (node (ref "R31") (pin "2") (pinfunction "2_2") (pintype "passive"))
    )
    (net (code "26") (name "Net-(IC5B-+IN)") (class "Default")
      (node (ref "C20") (pin "1") (pinfunction "1_1") (pintype "passive"))
      (node (ref "IC5") (pin "5") (pinfunction "+IN_5") (pintype "input"))
      (node (ref "R24") (pin "1") (pinfunction "1_1") (pintype "passive"))
    )
    (net (code "27") (name "Net-(IC5B--IN)") (class "Default")
      (node (ref "C19") (pin "2") (pinfunction "2_2") (pintype "passive"))
      (node (ref "IC5") (pin "6") (pinfunction "-IN_6") (pintype "input"))
      (node (ref "IC5") (pin "7") (pinfunction "OUT_7") (pintype "output"))
      (node (ref "R26") (pin "2") (pinfunction "2_2") (pintype "passive"))
    )
    (net (code "28") (name "Net-(LED1-PadA)") (class "Default")
      (node (ref "LED1") (pin "A") (pinfunction "A_A") (pintype "passive"))
      (node (ref "R2") (pin "1") (pinfunction "1_1") (pintype "passive"))
    )
    (net (code "29") (name "Net-(LED2-PadA)") (class "Default")
      (node (ref "LED2") (pin "A") (pinfunction "A_A") (pintype "passive"))
      (node (ref "R4") (pin "1") (pinfunction "1_1") (pintype "passive"))
    )
    (net (code "30") (name "Net-(LED3-PadA)") (class "Default")
      (node (ref "LED3") (pin "A") (pinfunction "A_A") (pintype "passive"))
      (node (ref "R6") (pin "1") (pinfunction "1_1") (pintype "passive"))
    )
    (net (code "31") (name "Net-(LED4-PadA)") (class "Default")
      (node (ref "LED4") (pin "A") (pinfunction "A_A") (pintype "passive"))
      (node (ref "R7") (pin "1") (pinfunction "1_1") (pintype "passive"))
    )
    (net (code "32") (name "Net-(LED5-PadA)") (class "Default")
      (node (ref "LED5") (pin "A") (pinfunction "A_A") (pintype "passive"))
      (node (ref "R8") (pin "1") (pinfunction "1_1") (pintype "passive"))
    )
    (net (code "33") (name "Net-(OUTA-PadTIP)") (class "Default")
      (node (ref "OUTA") (pin "TIP") (pinfunction "TIP_TIP") (pintype "passive"))
      (node (ref "R31") (pin "1") (pinfunction "1_1") (pintype "passive"))
    )
    (net (code "34") (name "Net-(OUTB-PadTIP)") (class "Default")
      (node (ref "OUTB") (pin "TIP") (pinfunction "TIP_TIP") (pintype "passive"))
      (node (ref "R20") (pin "1") (pinfunction "1_1") (pintype "passive"))
    )
    (net (code "35") (name "Net-(Q2-PadB)") (class "Default")
      (node (ref "Q2") (pin "B") (pinfunction "B_B") (pintype "passive"))
      (node (ref "R15") (pin "2") (pinfunction "2_2") (pintype "passive"))
    )
    (net (code "36") (name "Net-(Q3-PadB)") (class "Default")
      (node (ref "Q3") (pin "B") (pinfunction "B_B") (pintype "passive"))
      (node (ref "R27") (pin "2") (pinfunction "2_2") (pintype "passive"))
    )
    (net (code "37") (name "Net-(R10-Pad1)") (class "Default")
      (node (ref "R10") (pin "1") (pinfunction "1_1") (pintype "passive"))
      (node (ref "SW4") (pin "L1") (pinfunction "L1_L1") (pintype "passive"))
    )
    (net (code "38") (name "Net-(R15-Pad1)") (class "Default")
      (node (ref "R15") (pin "1") (pinfunction "1_1") (pintype "passive"))
      (node (ref "TRIG2") (pin "TIP") (pinfunction "TIP_TIP") (pintype "passive"))
    )
    (net (code "39") (name "Net-(R23-Pad1)") (class "Default")
      (node (ref "R23") (pin "1") (pinfunction "1_1") (pintype "passive"))
      (node (ref "SW6") (pin "L1") (pinfunction "L1_L1") (pintype "passive"))
    )
    (net (code "40") (name "Net-(R27-Pad1)") (class "Default")
      (node (ref "R27") (pin "1") (pinfunction "1_1") (pintype "passive"))
      (node (ref "TRIG1") (pin "TIP") (pinfunction "TIP_TIP") (pintype "passive"))
    )
    (net (code "41") (name "Net-(R32-A)") (class "Default")
      (node (ref "R30") (pin "2") (pinfunction "2_2") (pintype "passive"))
      (node (ref "R32") (pin "3") (pinfunction "A_3") (pintype "passive"))
    )
    (net (code "42") (name "Net-(R33-A)") (class "Default")
      (node (ref "R19") (pin "2") (pinfunction "2_2") (pintype "passive"))
      (node (ref "R33") (pin "3") (pinfunction "A_3") (pintype "passive"))
    )
    (net (code "43") (name "Net-(UC1-PA4{slash}SPI1_NSS{slash}USART2_CK{slash}ADC12_IN4)") (class "Default")
      (node (ref "R4") (pin "2") (pinfunction "2_2") (pintype "passive"))
      (node (ref "UC1") (pin "14") (pinfunction "PA4/SPI1_NSS/USART2_CK/ADC12_IN4_14") (pintype "bidirectional"))
    )
    (net (code "44") (name "Net-(UC1-PA5{slash}SPI1_SCK{slash}ADC12_IN5)") (class "Default")
      (node (ref "R6") (pin "2") (pinfunction "2_2") (pintype "passive"))
      (node (ref "UC1") (pin "15") (pinfunction "PA5/SPI1_SCK/ADC12_IN5_15") (pintype "bidirectional"))
    )
    (net (code "45") (name "Net-(UC1-PA6{slash}SPI1_MISO{slash}ADC12_IN6{slash}TIM3_CH1)") (class "Default")
      (node (ref "R7") (pin "2") (pinfunction "2_2") (pintype "passive"))
      (node (ref "UC1") (pin "16") (pinfunction "PA6/SPI1_MISO/ADC12_IN6/TIM3_CH1_16") (pintype "bidirectional"))
    )
    (net (code "46") (name "Net-(UC1-PA7{slash}SPI1_MOSI{slash}ADC12_IN7{slash}TIM3_CH2)") (class "Default")
      (node (ref "R8") (pin "2") (pinfunction "2_2") (pintype "passive"))
      (node (ref "UC1") (pin "17") (pinfunction "PA7/SPI1_MOSI/ADC12_IN7/TIM3_CH2_17") (pintype "bidirectional"))
    )
    (net (code "47") (name "Net-(UC1-PB0{slash}ADC12_IN8{slash}TIM3_CH3)") (class "Default")
      (node (ref "R23") (pin "2") (pinfunction "2_2") (pintype "passive"))
      (node (ref "UC1") (pin "18") (pinfunction "PB0/ADC12_IN8/TIM3_CH3_18") (pintype "bidirectional"))
    )
    (net (code "48") (name "Net-(UC1-PB1{slash}ADC12_IN9{slash}TIM3_CH4)") (class "Default")
      (node (ref "R10") (pin "2") (pinfunction "2_2") (pintype "passive"))
      (node (ref "UC1") (pin "19") (pinfunction "PB1/ADC12_IN9/TIM3_CH4_19") (pintype "bidirectional"))
    )
    (net (code "49") (name "Net-(UC1-PB10{slash}I2C2_SCL{slash}USART3_TX)") (class "Default")
      (node (ref "R2") (pin "2") (pinfunction "2_2") (pintype "passive"))
      (node (ref "UC1") (pin "21") (pinfunction "PB10/I2C2_SCL/USART3_TX_21") (pintype "input"))
    )
    (net (code "50") (name "Net-(UC1-PD0-OSC_IN)") (class "Default")
      (node (ref "C7") (pin "2") (pinfunction "2_2") (pintype "passive"))
      (node (ref "Q1") (pin "2") (pinfunction "2_2") (pintype "passive"))
      (node (ref "UC1") (pin "5") (pinfunction "PD0-OSC_IN_5") (pintype "input"))
    )
    (net (code "51") (name "Net-(UC1-PD1-OSC_OUT)") (class "Default")
      (node (ref "C6") (pin "2") (pinfunction "2_2") (pintype "passive"))
      (node (ref "Q1") (pin "1") (pinfunction "1_1") (pintype "passive"))
      (node (ref "UC1") (pin "6") (pinfunction "PD1-OSC_OUT_6") (pintype "input"))
    )
    (net (code "52") (name "POT_1") (class "Default")
      (node (ref "R1") (pin "P$2") (pinfunction "S_P$2") (pintype "passive"))
      (node (ref "UC1") (pin "13") (pinfunction "PA3/USART2_RX/ADC12_IN3/TIM2_CH4_13") (pintype "bidirectional"))
    )
    (net (code "53") (name "POT_2") (class "Default")
      (node (ref "R5") (pin "P$2") (pinfunction "S_P$2") (pintype "passive"))
      (node (ref "UC1") (pin "12") (pinfunction "PA2/USART2_TX/ADC12_IN2/TIM2_CH3_12") (pintype "bidirectional"))
    )
    (net (code "54") (name "POT_3") (class "Default")
      (node (ref "R11") (pin "P$2") (pinfunction "S_P$2") (pintype "passive"))
      (node (ref "UC1") (pin "11") (pinfunction "PA1/USART2_RTS/ADC12_IN1/TIM2_CH2_11") (pintype "bidirectional"))
    )
    (net (code "55") (name "POT_4") (class "Default")
      (node (ref "R21") (pin "P$2") (pinfunction "S_P$2") (pintype "passive"))
      (node (ref "UC1") (pin "10") (pinfunction "PA0_WKUP/USART2_CTS/ADC12_IN0/TIM2_CH1_ETR_10") (pintype "bidirectional"))
    )
    (net (code "56") (name "RESET") (class "Default")
      (node (ref "JP2") (pin "10") (pinfunction "10_10") (pintype "passive"))
      (node (ref "R3") (pin "1") (pinfunction "1_1") (pintype "passive"))
      (node (ref "SW3") (pin "B") (pinfunction "S_B") (pintype "passive"))
      (node (ref "SW3") (pin "B'") (pinfunction "S1_B'") (pintype "passive"))
      (node (ref "UC1") (pin "7") (pinfunction "NRST_7") (pintype "input"))
    )
    (net (code "57") (name "RX") (class "Default")
      (node (ref "JP1") (pin "4") (pinfunction "4_4") (pintype "passive"))
      (node (ref "UC1") (pin "31") (pinfunction "PA10/USART1_RX/TIM1_CH3_31") (pintype "bidirectional"))
    )
    (net (code "58") (name "SW_DUAL") (class "Default")
      (node (ref "SW2") (pin "3") (pinfunction "3_3") (pintype "passive"))
      (node (ref "SW2") (pin "4") (pinfunction "4_4") (pintype "passive"))
      (node (ref "UC1") (pin "3") (pinfunction "PC14-OSC32_IN_3") (pintype "input"))
    )
    (net (code "59") (name "SW_MODE") (class "Default")
      (node (ref "SW1") (pin "3") (pinfunction "3_3") (pintype "passive"))
      (node (ref "SW1") (pin "4") (pinfunction "4_4") (pintype "passive"))
      (node (ref "UC1") (pin "2") (pinfunction "PC13-TAMPER-RTC_2") (pintype "input"))
    )
    (net (code "60") (name "SW_TRIG_1") (class "Default")
      (node (ref "SW6") (pin "P2") (pinfunction "A2_P2") (pintype "passive"))
      (node (ref "SW6") (pin "P5") (pinfunction "B2_P5") (pintype "passive"))
      (node (ref "UC1") (pin "40") (pinfunction "PB4/NJTRST_40") (pintype "bidirectional"))
    )
    (net (code "61") (name "SW_TRIG_2") (class "Default")
      (node (ref "SW4") (pin "P2") (pinfunction "A2_P2") (pintype "passive"))
      (node (ref "SW4") (pin "P5") (pinfunction "B2_P5") (pintype "passive"))
      (node (ref "UC1") (pin "29") (pinfunction "PA8/USART1_CK/TIM1_CH1/MCO_29") (pintype "bidirectional"))
    )
    (net (code "62") (name "TRIG_1") (class "Default")
      (node (ref "Q3") (pin "C") (pinfunction "C_C") (pintype "passive"))
      (node (ref "R28") (pin "1") (pinfunction "1_1") (pintype "passive"))
      (node (ref "UC1") (pin "33") (pinfunction "PA12/USART1_RTS/CAN_TX/TIM1_ETR/USBDP_33") (pintype "bidirectional"))
    )
    (net (code "63") (name "TRIG_2") (class "Default")
      (node (ref "Q2") (pin "C") (pinfunction "C_C") (pintype "passive"))
      (node (ref "R16") (pin "1") (pinfunction "1_1") (pintype "passive"))
      (node (ref "UC1") (pin "22") (pinfunction "PB11/I2C2_SDA/USART3_RX_22") (pintype "input"))
    )
    (net (code "64") (name "TX") (class "Default")
      (node (ref "JP1") (pin "5") (pinfunction "5_5") (pintype "passive"))
      (node (ref "UC1") (pin "30") (pinfunction "PA9/USART1_TX/TIM1_CH2_30") (pintype "input"))
    )
    (net (code "65") (name "VCC") (class "Default")
      (node (ref "C16") (pin "1") (pinfunction "1_1") (pintype "passive"))
      (node (ref "C2") (pin "+") (pinfunction "+_+") (pintype "passive"))
      (node (ref "C21") (pin "1") (pinfunction "1_1") (pintype "passive"))
      (node (ref "D1") (pin "C") (pinfunction "C_C") (pintype "passive"))
      (node (ref "IC1") (pin "3") (pinfunction "VIN_3") (pintype "input"))
      (node (ref "IC4") (pin "8") (pinfunction "V+_8") (pintype "power_in"))
      (node (ref "IC5") (pin "8") (pinfunction "V+_8") (pintype "power_in"))
    )
    (net (code "66") (name "VEE") (class "Default")
      (node (ref "C1") (pin "-") (pinfunction "-_-") (pintype "passive"))
      (node (ref "C18") (pin "2") (pinfunction "2_2") (pintype "passive"))
      (node (ref "C24") (pin "2") (pinfunction "2_2") (pintype "passive"))
      (node (ref "D2") (pin "A") (pinfunction "A_A") (pintype "passive"))
      (node (ref "IC4") (pin "4") (pinfunction "V-_4") (pintype "power_in"))
      (node (ref "IC5") (pin "4") (pinfunction "V-_4") (pintype "power_in"))
      (node (ref "R25") (pin "1") (pinfunction "1_1") (pintype "passive"))
    )
    (net (code "67") (name "unconnected-(JP1-Pad2)") (class "Default")
      (node (ref "JP1") (pin "2") (pinfunction "2_2") (pintype "passive"))
    )
    (net (code "68") (name "unconnected-(JP1-Pad3)") (class "Default")
      (node (ref "JP1") (pin "3") (pinfunction "3_3") (pintype "passive"))
    )
    (net (code "69") (name "unconnected-(JP1-Pad6)") (class "Default")
      (node (ref "JP1") (pin "6") (pinfunction "6_6") (pintype "passive"))
    )
    (net (code "70") (name "unconnected-(JP2-Pad7)") (class "Default")
      (node (ref "JP2") (pin "7") (pinfunction "7_7") (pintype "passive"))
    )
    (net (code "71") (name "unconnected-(OUTA-SWITCH-PadDESC)") (class "Default")
      (node (ref "OUTA") (pin "DESC") (pinfunction "SWITCH_DESC") (pintype "passive"))
    )
    (net (code "72") (name "unconnected-(OUTB-SWITCH-PadDESC)") (class "Default")
      (node (ref "OUTB") (pin "DESC") (pinfunction "SWITCH_DESC") (pintype "passive"))
    )
    (net (code "73") (name "unconnected-(SW4A-A1-PadP1)") (class "Default")
      (node (ref "SW4") (pin "P1") (pinfunction "A1_P1") (pintype "passive"))
    )
    (net (code "74") (name "unconnected-(SW4A-B1-PadP4)") (class "Default")
      (node (ref "SW4") (pin "P4") (pinfunction "B1_P4") (pintype "passive"))
    )
    (net (code "75") (name "unconnected-(SW6A-A1-PadP1)") (class "Default")
      (node (ref "SW6") (pin "P1") (pinfunction "A1_P1") (pintype "passive"))
    )
    (net (code "76") (name "unconnected-(SW6A-B1-PadP4)") (class "Default")
      (node (ref "SW6") (pin "P4") (pinfunction "B1_P4") (pintype "passive"))
    )
    (net (code "77") (name "unconnected-(UC1-PA11{slash}USART1_CTS{slash}CAN_RX{slash}TIM1_CH4{slash}USBDM-Pad32)") (class "Default")
      (node (ref "UC1") (pin "32") (pinfunction "PA11/USART1_CTS/CAN_RX/TIM1_CH4/USBDM_32") (pintype "bidirectional"))
    )
    (net (code "78") (name "unconnected-(UC1-PB5{slash}I2C1_SMBA-Pad41)") (class "Default")
      (node (ref "UC1") (pin "41") (pinfunction "PB5/I2C1_SMBA_41") (pintype "input"))
    )
    (net (code "79") (name "unconnected-(UC1-PB6{slash}I2C1_SCL{slash}TIM4_CH1-Pad42)") (class "Default")
      (node (ref "UC1") (pin "42") (pinfunction "PB6/I2C1_SCL/TIM4_CH1_42") (pintype "input"))
    )
    (net (code "80") (name "unconnected-(UC1-PB7{slash}I2C1_SDA{slash}TIM4_CH2-Pad43)") (class "Default")
      (node (ref "UC1") (pin "43") (pinfunction "PB7/I2C1_SDA/TIM4_CH2_43") (pintype "bidirectional"))
    )
    (net (code "81") (name "unconnected-(UC1-PB8{slash}TIM4_CH3-Pad45)") (class "Default")
      (node (ref "UC1") (pin "45") (pinfunction "PB8/TIM4_CH3_45") (pintype "bidirectional"))
    )
    (net (code "82") (name "unconnected-(UC1-PB9{slash}TIM4_CH4-Pad46)") (class "Default")
      (node (ref "UC1") (pin "46") (pinfunction "PB9/TIM4_CH4_46") (pintype "input"))
    )
    (net (code "83") (name "unconnected-(UC1-PB14{slash}SPI2_MISO{slash}USART3_RTS{slash}TIM1_CH2N-Pad27)") (class "Default")
      (node (ref "UC1") (pin "27") (pinfunction "PB14/SPI2_MISO/USART3_RTS/TIM1_CH2N_27") (pintype "input"))
    )
    (net (code "84") (name "unconnected-(UC1-PC15-OSC32_OUT-Pad4)") (class "Default")
      (node (ref "UC1") (pin "4") (pinfunction "PC15-OSC32_OUT_4") (pintype "input"))
    )
  )
)
